# buffer.net
KiCad netlist of a schematic drawn in Altium Designer
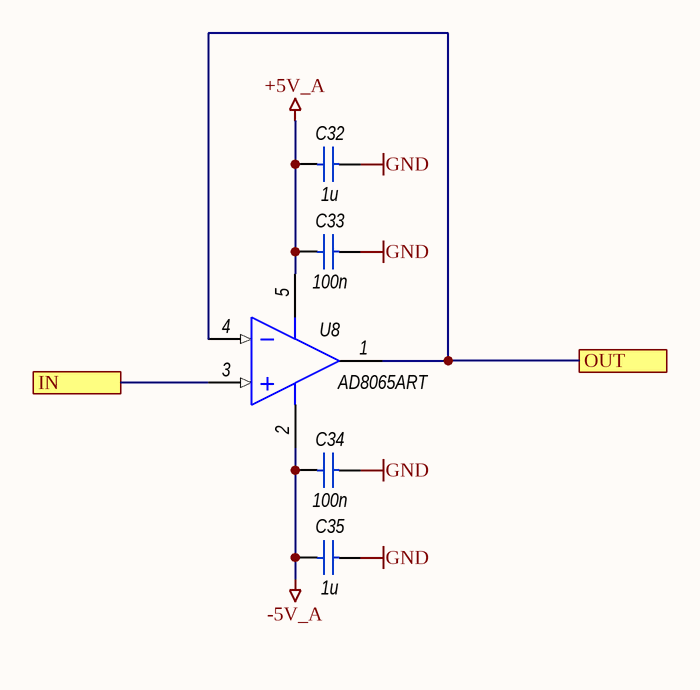
[diagram p0: buffer.SchDoc]

(export (version "E")
  (design (tool "Eeschema 10.0.6"))
  (components
    (comp (ref "C32")
      (value "1u")
      (footprint "CAP_0603")
      (description "Конденсатор")
      (libsource (lib "SCH_LIB") (part "Capacitor"))
    )
    (comp (ref "C33")
      (value "100n")
      (footprint "CAP_0603")
      (description "Конденсатор")
      (libsource (lib "SCH_LIB") (part "Capacitor"))
    )
    (comp (ref "C34")
      (value "100n")
      (footprint "CAP_0603")
      (description "Конденсатор")
      (libsource (lib "SCH_LIB") (part "Capacitor"))
    )
    (comp (ref "C35")
      (value "1u")
      (footprint "CAP_0603")
      (description "Конденсатор")
      (libsource (lib "SCH_LIB") (part "Capacitor"))
    )
    (comp (ref "U8")
      (value "AD8065ART")
      (footprint "sot235")
      (description "Операционный усилитель")
      (libsource (lib "SCH_LIB") (part "OPAMP SOT235"))
    )
  )
  (nets
    (net (code "1") (name "+5V_A") (class "Default")
      (node (ref "C32") (pin "1") (pinfunction "1_1") (pintype "passive"))
      (node (ref "C33") (pin "1") (pinfunction "1_1") (pintype "passive"))
      (node (ref "U8") (pin "5") (pinfunction "V+_5") (pintype "power_in"))
    )
    (net (code "2") (name "-5V_A") (class "Default")
      (node (ref "C34") (pin "1") (pinfunction "1_1") (pintype "passive"))
      (node (ref "C35") (pin "1") (pinfunction "1_1") (pintype "passive"))
      (node (ref "U8") (pin "2") (pinfunction "V-_2") (pintype "power_in"))
    )
    (net (code "3") (name "/IN") (class "Default")
      (node (ref "U8") (pin "3") (pinfunction "IN+_3") (pintype "input"))
    )
    (net (code "4") (name "/OUT") (class "Default")
      (node (ref "U8") (pin "1") (pinfunction "OUT_1") (pintype "open_collector"))
      (node (ref "U8") (pin "4") (pinfunction "IN-_4") (pintype "input"))
    )
    (net (code "5") (name "GND") (class "Default")
      (node (ref "C32") (pin "2") (pinfunction "2_2") (pintype "passive"))
      (node (ref "C33") (pin "2") (pinfunction "2_2") (pintype "passive"))
      (node (ref "C34") (pin "2") (pinfunction "2_2") (pintype "passive"))
      (node (ref "C35") (pin "2") (pinfunction "2_2") (pintype "passive"))
    )
  )
)
